# JP_WING_L.net
KiCad netlist of a schematic drawn in EasyEDA Pro
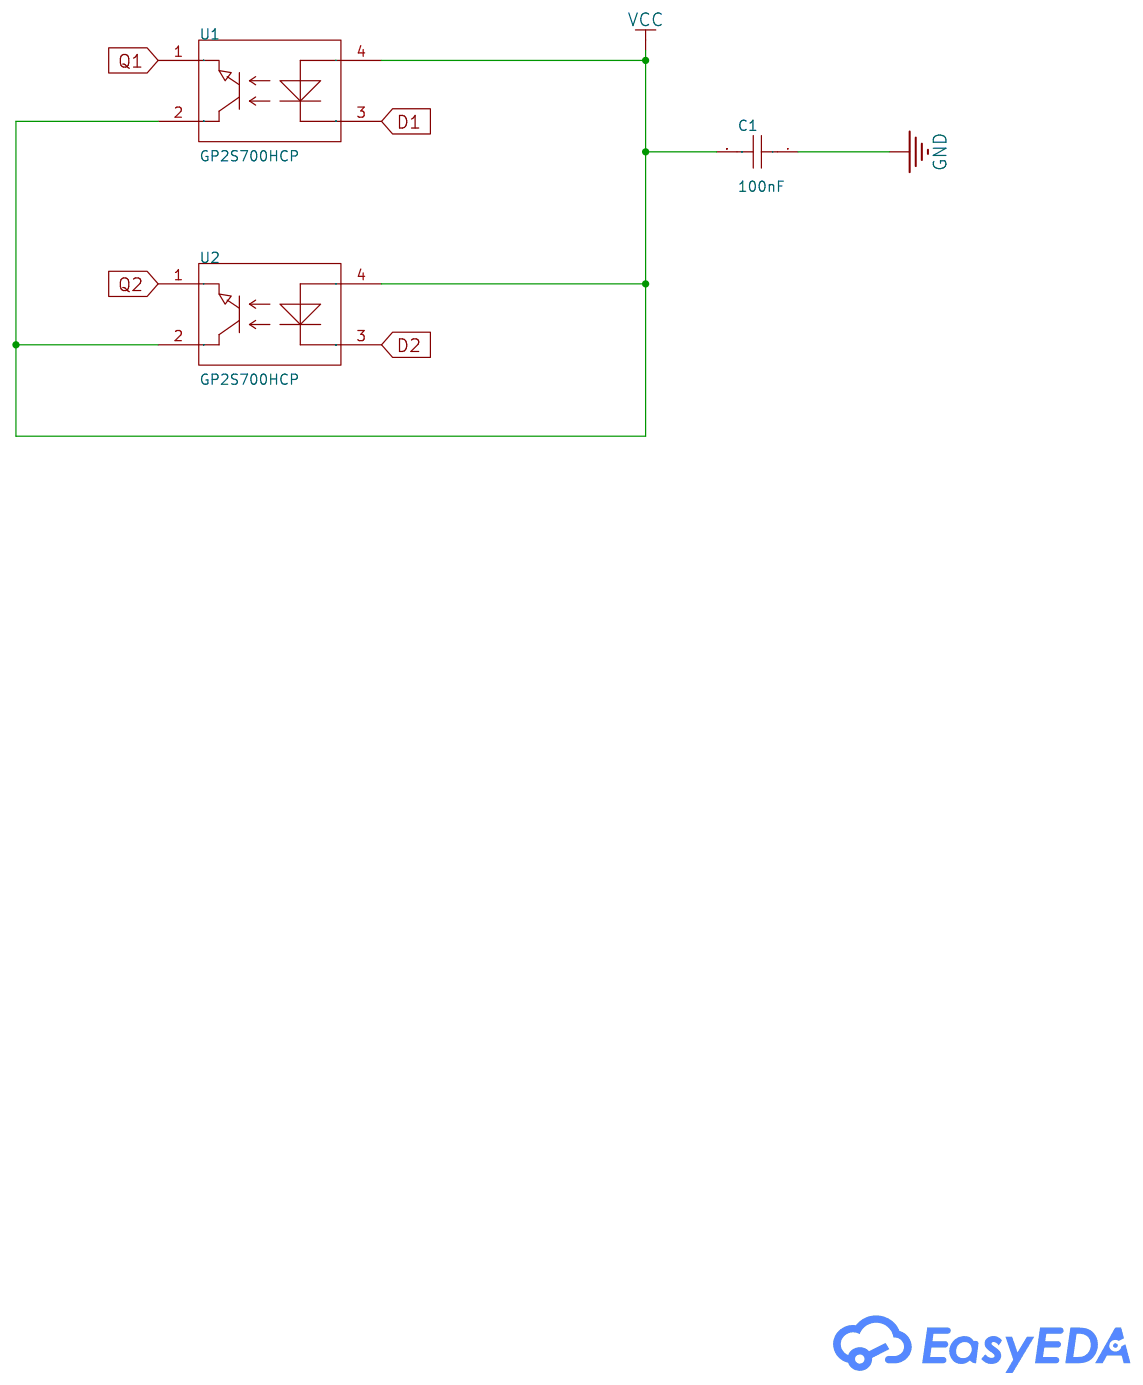
[diagram p0: schematic sheet]

(export (version "E")
  (design (tool "Eeschema 10.0.6"))
  (components
    (comp (ref "C1")
      (value "100nF")
      (footprint "easyedapro:C0603")
      (libsource (lib "easyedapro") (part "CAP"))
    )
    (comp (ref "U1")
      (value "GP2S700HCP")
      (footprint "easyedapro:OPTO-SMD_GP2S700HCP")
      (description "Sensing Distance:5.5mm Collector Current (Max):20mA")
      (fields (field (name "Manufacturer") "SHARP(夏普)"))
      (libsource (lib "easyedapro") (part "GP2S700HCP"))
    )
    (comp (ref "U2")
      (value "GP2S700HCP")
      (footprint "easyedapro:OPTO-SMD_GP2S700HCP")
      (description "Sensing Distance:5.5mm Collector Current (Max):20mA")
      (fields (field (name "Manufacturer") "SHARP(夏普)"))
      (libsource (lib "easyedapro") (part "GP2S700HCP"))
    )
  )
  (nets
    (net (code "1") (name "D1") (class "Default")
      (node (ref "U1") (pin "3") (pinfunction "3_3") (pintype "input"))
    )
    (net (code "2") (name "D2") (class "Default")
      (node (ref "U2") (pin "3") (pinfunction "3_3") (pintype "input"))
    )
    (net (code "3") (name "GND") (class "Default")
      (node (ref "C1") (pin "1") (pinfunction "1_1") (pintype "input"))
    )
    (net (code "4") (name "Q1") (class "Default")
      (node (ref "U1") (pin "1") (pinfunction "1_1") (pintype "input"))
    )
    (net (code "5") (name "Q2") (class "Default")
      (node (ref "U2") (pin "1") (pinfunction "1_1") (pintype "input"))
    )
    (net (code "6") (name "VCC") (class "Default")
      (node (ref "C1") (pin "2") (pinfunction "2_2") (pintype "input"))
      (node (ref "U1") (pin "2") (pinfunction "2_2") (pintype "input"))
      (node (ref "U1") (pin "4") (pinfunction "4_4") (pintype "input"))
      (node (ref "U2") (pin "2") (pinfunction "2_2") (pintype "input"))
      (node (ref "U2") (pin "4") (pinfunction "4_4") (pintype "input"))
    )
  )
)
